# V1d.net
KiCad netlist of a schematic drawn in EAGLE
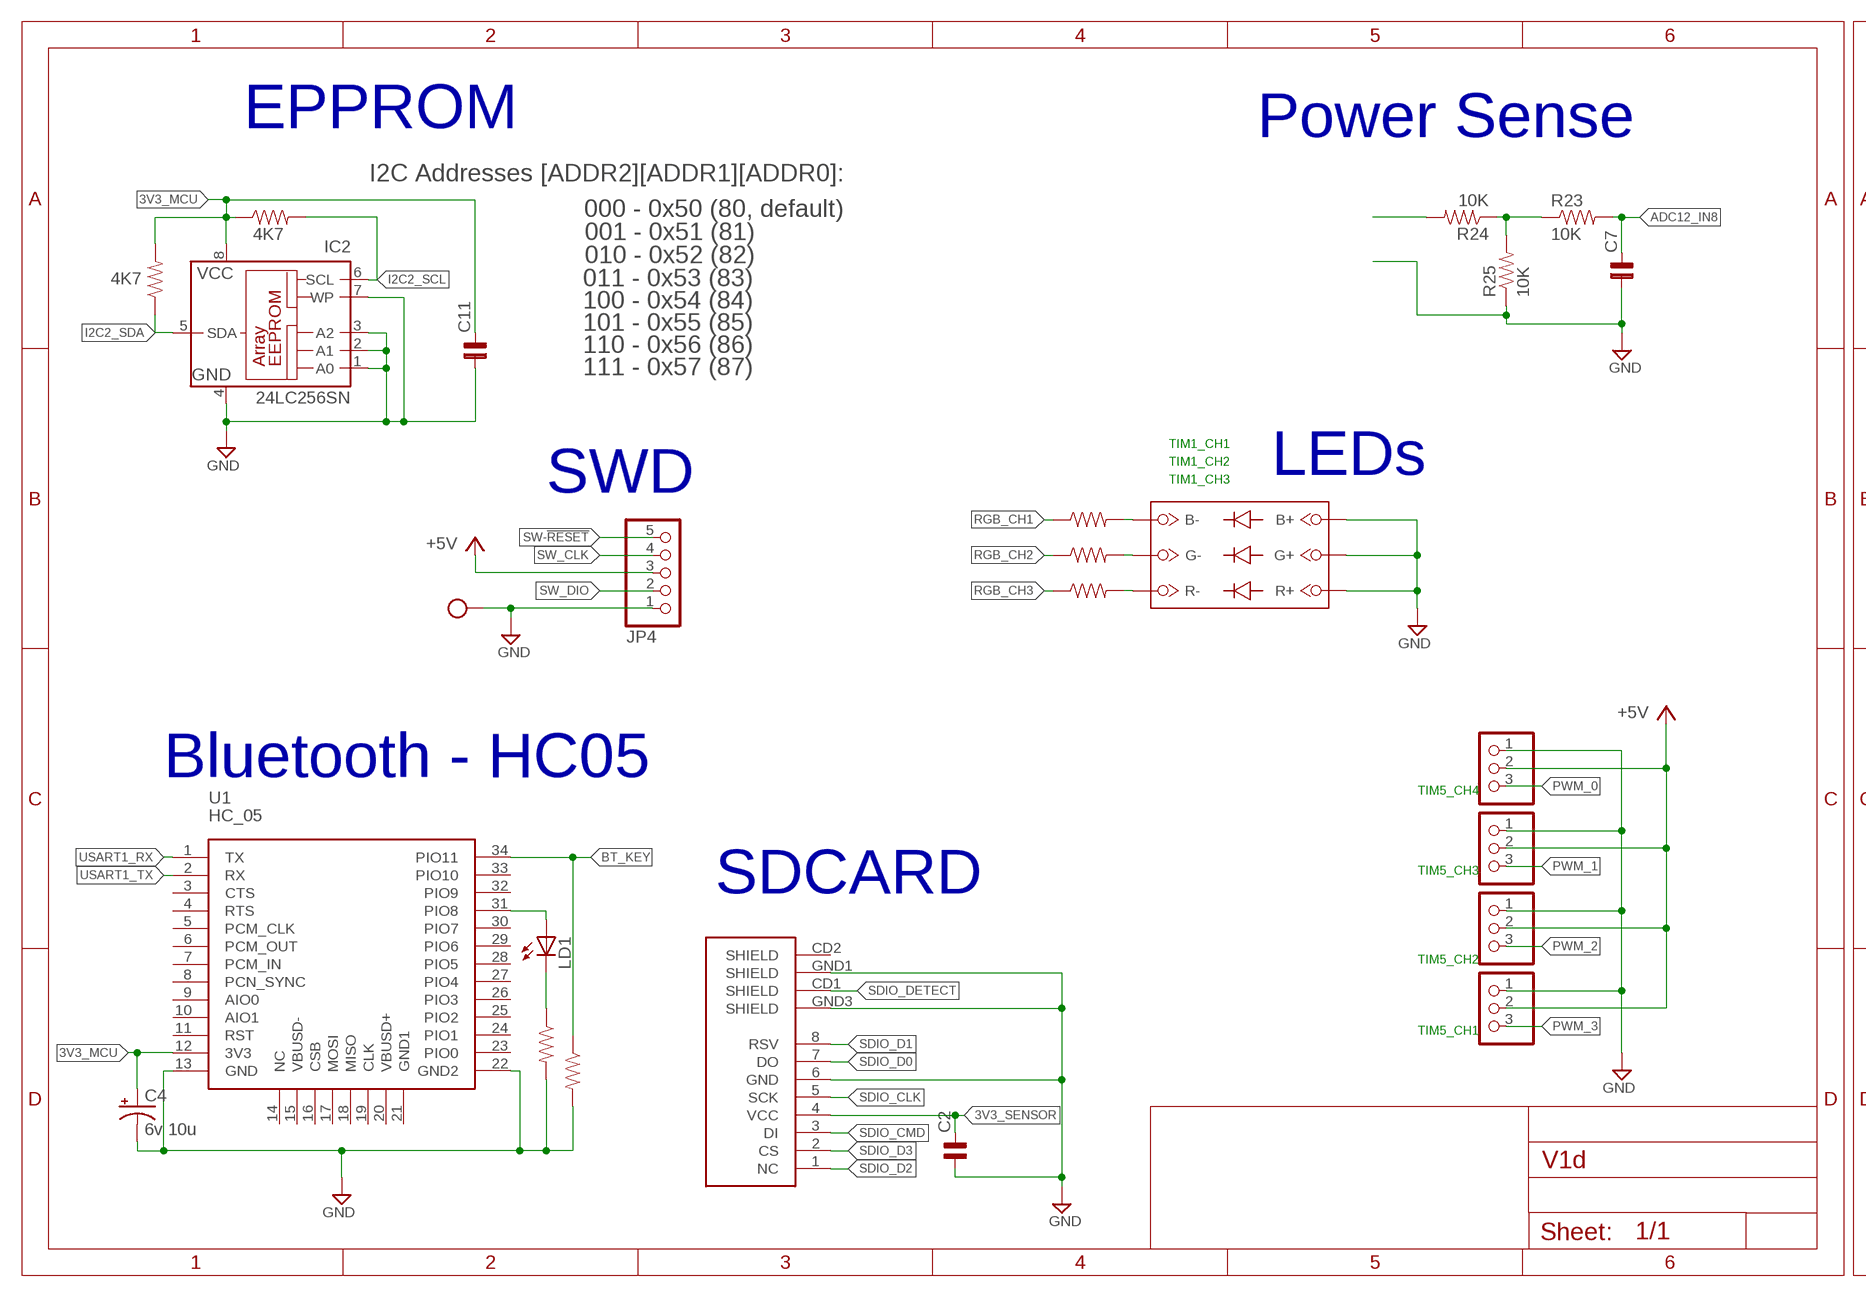
[diagram p0: schematic, sheet 1, part 1 of 2]
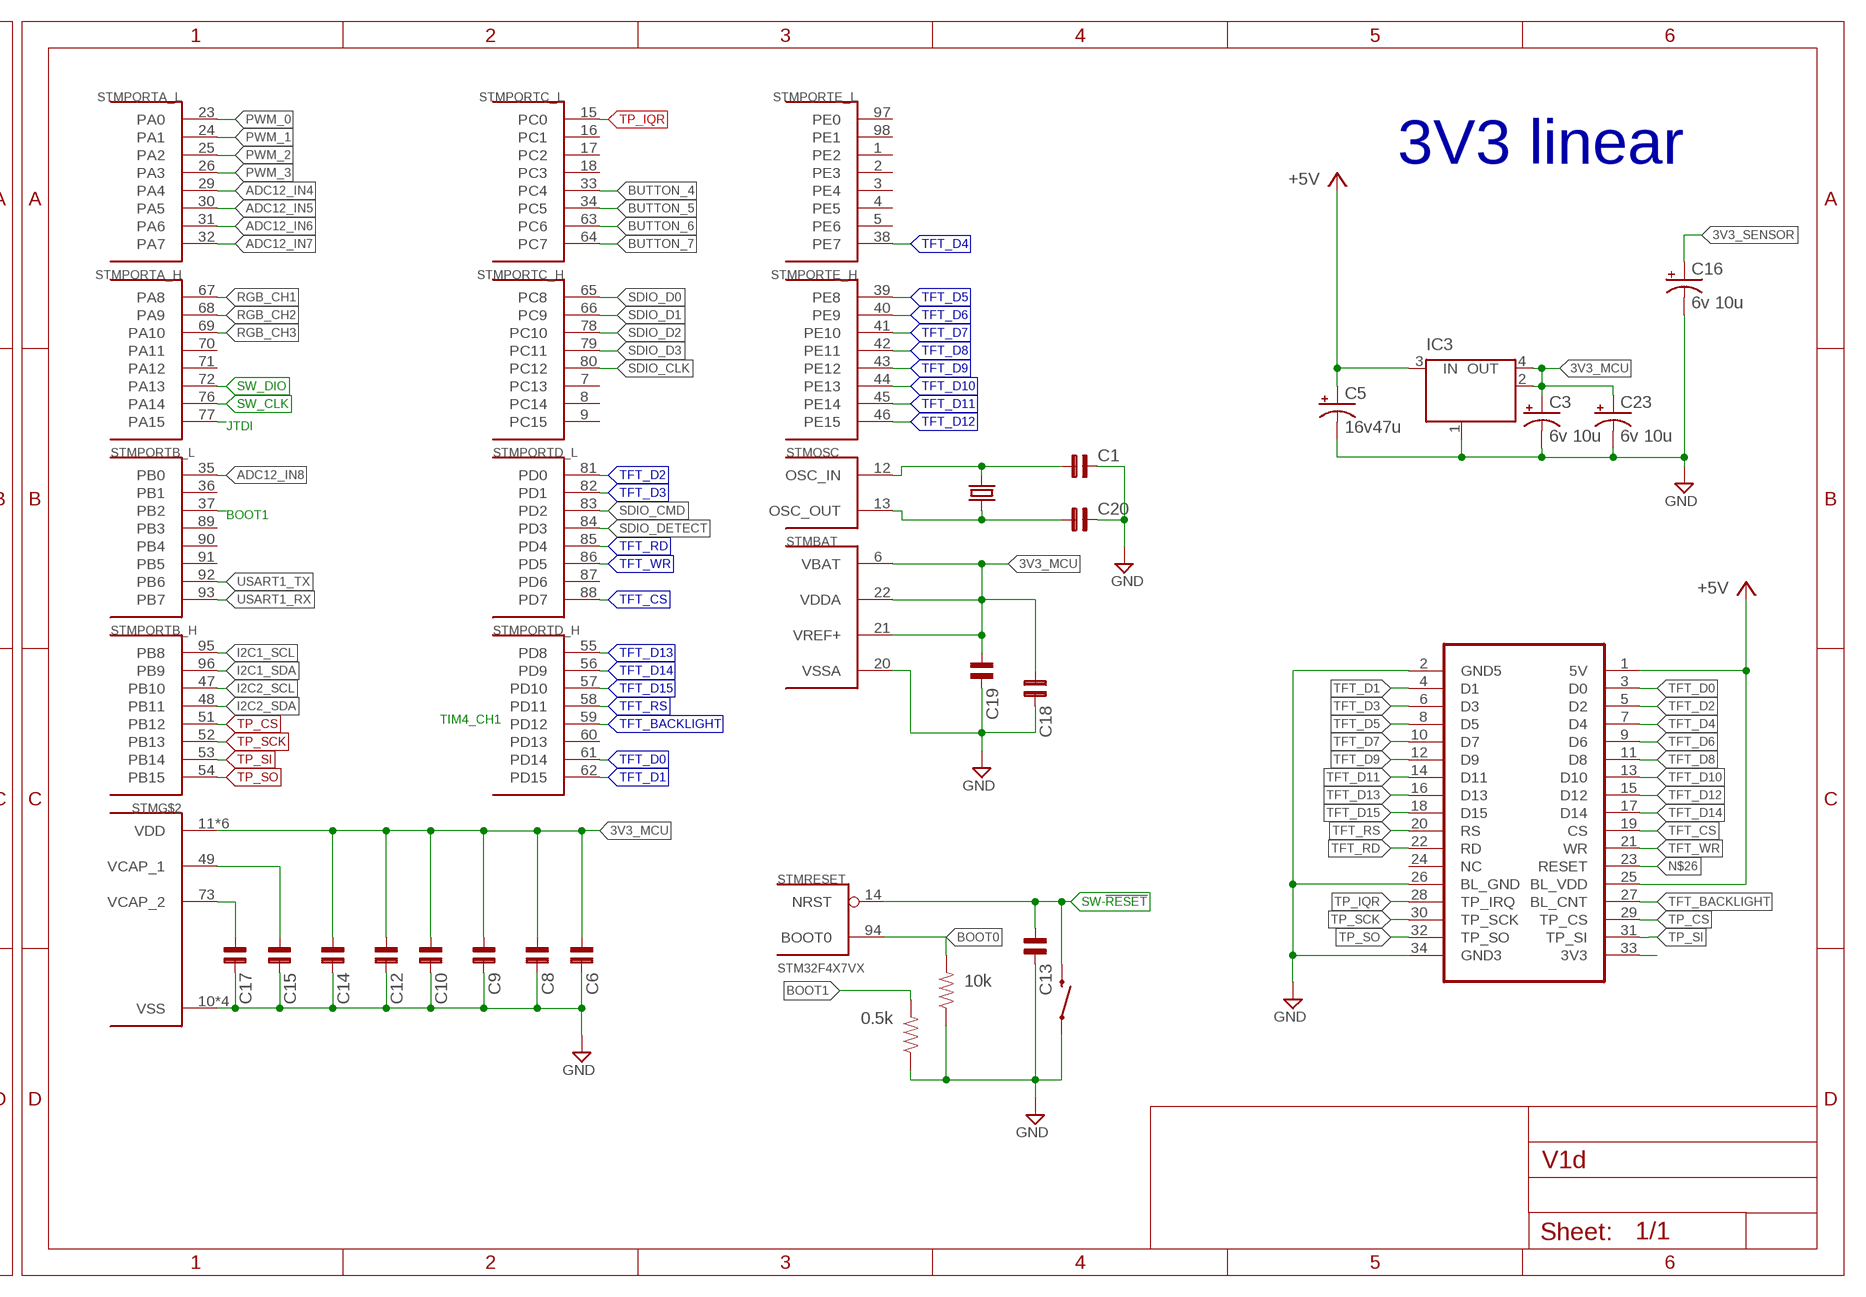
[diagram p1: schematic, sheet 1, part 2 of 2]

(export (version "E")
  (design (tool "Eeschema 10.0.6"))
  (components
    (comp (ref "C1")
      (value "C-NP-SMD-0603")
      (footprint "eagle-import:C-0603")
      (libsource (lib "eagle-import") (part "C-NP-SMD-0603"))
    )
    (comp (ref "C2")
      (value "C-NP-SMD-0603")
      (footprint "eagle-import:C-0603")
      (libsource (lib "eagle-import") (part "C-NP-SMD-0603"))
    )
    (comp (ref "C3")
      (value "6v 10u")
      (footprint "eagle-import:SMC_A")
      (libsource (lib "eagle-import") (part "CPOL-USSMCA"))
    )
    (comp (ref "C4")
      (value "6v 10u")
      (footprint "eagle-import:SMC_A")
      (libsource (lib "eagle-import") (part "CPOL-USSMCA"))
    )
    (comp (ref "C5")
      (value "16v47u")
      (footprint "eagle-import:SMC_C")
      (libsource (lib "eagle-import") (part "CPOL-USSMCC"))
    )
    (comp (ref "C6")
      (value "C-NP-SMD-0603")
      (footprint "eagle-import:C-0603")
      (libsource (lib "eagle-import") (part "C-NP-SMD-0603"))
    )
    (comp (ref "C7")
      (value "C-NP-SMD-0603")
      (footprint "eagle-import:C-0603")
      (libsource (lib "eagle-import") (part "C-NP-SMD-0603"))
    )
    (comp (ref "C8")
      (value "C-NP-SMD-0603")
      (footprint "eagle-import:C-0603")
      (libsource (lib "eagle-import") (part "C-NP-SMD-0603"))
    )
    (comp (ref "C9")
      (value "C-NP-SMD-0603")
      (footprint "eagle-import:C-0603")
      (libsource (lib "eagle-import") (part "C-NP-SMD-0603"))
    )
    (comp (ref "C10")
      (value "C-NP-SMD-0603")
      (footprint "eagle-import:C-0603")
      (libsource (lib "eagle-import") (part "C-NP-SMD-0603"))
    )
    (comp (ref "C11")
      (value "C-NP-SMD-0603")
      (footprint "eagle-import:C-0603")
      (libsource (lib "eagle-import") (part "C-NP-SMD-0603"))
    )
    (comp (ref "C12")
      (value "C-NP-SMD-0603")
      (footprint "eagle-import:C-0603")
      (libsource (lib "eagle-import") (part "C-NP-SMD-0603"))
    )
    (comp (ref "C13")
      (value "C-NP-SMD-0603")
      (footprint "eagle-import:C-0603")
      (libsource (lib "eagle-import") (part "C-NP-SMD-0603"))
    )
    (comp (ref "C14")
      (value "C-NP-SMD-0603")
      (footprint "eagle-import:C-0603")
      (libsource (lib "eagle-import") (part "C-NP-SMD-0603"))
    )
    (comp (ref "C15")
      (value "C-NP-SMD-0603")
      (footprint "eagle-import:C-0603")
      (libsource (lib "eagle-import") (part "C-NP-SMD-0603"))
    )
    (comp (ref "C16")
      (value "6v 10u")
      (footprint "eagle-import:SMC_A")
      (libsource (lib "eagle-import") (part "CPOL-USSMCA"))
    )
    (comp (ref "C17")
      (value "C-NP-SMD-0603")
      (footprint "eagle-import:C-0603")
      (libsource (lib "eagle-import") (part "C-NP-SMD-0603"))
    )
    (comp (ref "C18")
      (value "C-NP-SMD-0603")
      (footprint "eagle-import:C-0603")
      (libsource (lib "eagle-import") (part "C-NP-SMD-0603"))
    )
    (comp (ref "C19")
      (value "C-NP-SMD-0603")
      (footprint "eagle-import:C-0603")
      (libsource (lib "eagle-import") (part "C-NP-SMD-0603"))
    )
    (comp (ref "C20")
      (value "C-NP-SMD-0603")
      (footprint "eagle-import:C-0603")
      (libsource (lib "eagle-import") (part "C-NP-SMD-0603"))
    )
    (comp (ref "C23")
      (value "6v 10u")
      (footprint "eagle-import:SMC_A")
      (libsource (lib "eagle-import") (part "CPOL-USSMCA"))
    )
    (comp (ref "IC2")
      (value "24LC256SN")
      (footprint "eagle-import:SO-08")
      (fields (field (name "MF") "MICROCHIP") (field (name "MPN") "24LC256-I/SN"))
      (libsource (lib "eagle-import") (part "24SNLC256"))
    )
    (comp (ref "IC3")
      (value "LINEAR_MC33269ST-3.3T3")
      (footprint "eagle-import:LINEAR_SOT223")
      (libsource (lib "eagle-import") (part "LINEAR_MC33269ST-3.3T3"))
    )
    (comp (ref "JP1")
      (value "PINHD-1X3_2.54-90°")
      (footprint "eagle-import:1X03_90")
      (libsource (lib "eagle-import") (part "PINHD-1X3_2.54-90°"))
    )
    (comp (ref "JP4")
      (value "PINHD-1X5_2.54-90°")
      (footprint "eagle-import:1X05_90")
      (libsource (lib "eagle-import") (part "PINHD-1X5_2.54-90°"))
    )
    (comp (ref "JP5")
      (value "PINHD-1X3_2.54-90°")
      (footprint "eagle-import:1X03_90")
      (libsource (lib "eagle-import") (part "PINHD-1X3_2.54-90°"))
    )
    (comp (ref "JP6")
      (value "PINHD-1X3_2.54-90°")
      (footprint "eagle-import:1X03_90")
      (libsource (lib "eagle-import") (part "PINHD-1X3_2.54-90°"))
    )
    (comp (ref "JP11")
      (value "PINHD-1X3_2.54-90°")
      (footprint "eagle-import:1X03_90")
      (libsource (lib "eagle-import") (part "PINHD-1X3_2.54-90°"))
    )
    (comp (ref "LD1")
      (value "LEDCHIPLED_0805")
      (footprint "eagle-import:CHIPLED_0805")
      (libsource (lib "eagle-import") (part "LEDCHIPLED_0805"))
    )
    (comp (ref "R2")
      (value "10K")
      (footprint "eagle-import:SPARKFUN_0603-RES")
      (libsource (lib "eagle-import") (part "SPARKFUN_RESISTOR0603-RES"))
    )
    (comp (ref "R3")
      (value "10K")
      (footprint "eagle-import:SPARKFUN_0603-RES")
      (libsource (lib "eagle-import") (part "SPARKFUN_RESISTOR0603-RES"))
    )
    (comp (ref "R5")
      (value "10K")
      (footprint "eagle-import:SPARKFUN_0603-RES")
      (libsource (lib "eagle-import") (part "SPARKFUN_RESISTOR0603-RES"))
    )
    (comp (ref "R6")
      (value "10K")
      (footprint "eagle-import:SPARKFUN_0603-RES")
      (libsource (lib "eagle-import") (part "SPARKFUN_RESISTOR0603-RES"))
    )
    (comp (ref "R7")
      (value "10k")
      (footprint "eagle-import:SPARKFUN_0603-RES")
      (libsource (lib "eagle-import") (part "SPARKFUN_RESISTOR0603-RES"))
    )
    (comp (ref "R8")
      (value "0.5k")
      (footprint "eagle-import:SPARKFUN_0603-RES")
      (libsource (lib "eagle-import") (part "SPARKFUN_RESISTOR0603-RES"))
    )
    (comp (ref "R9")
      (value "10K")
      (footprint "eagle-import:SPARKFUN_0603-RES")
      (libsource (lib "eagle-import") (part "SPARKFUN_RESISTOR0603-RES"))
    )
    (comp (ref "R15")
      (value "4K7")
      (footprint "eagle-import:SPARKFUN_0603-RES")
      (libsource (lib "eagle-import") (part "SPARKFUN_RESISTOR0603-RES"))
    )
    (comp (ref "R16")
      (value "4K7")
      (footprint "eagle-import:SPARKFUN_0603-RES")
      (libsource (lib "eagle-import") (part "SPARKFUN_RESISTOR0603-RES"))
    )
    (comp (ref "R23")
      (value "10K")
      (footprint "eagle-import:SPARKFUN_0603-RES")
      (libsource (lib "eagle-import") (part "SPARKFUN_RESISTOR0603-RES"))
    )
    (comp (ref "R24")
      (value "10K")
      (footprint "eagle-import:SPARKFUN_0603-RES")
      (libsource (lib "eagle-import") (part "SPARKFUN_RESISTOR0603-RES"))
    )
    (comp (ref "R25")
      (value "10K")
      (footprint "eagle-import:SPARKFUN_0603-RES")
      (libsource (lib "eagle-import") (part "SPARKFUN_RESISTOR0603-RES"))
    )
    (comp (ref "S1")
      (value "RESET")
      (footprint "eagle-import:TACTILE-SWITCH-1101NE")
      (fields (field (name "PARTNO") "EVQ-P7J01P"))
      (libsource (lib "eagle-import") (part "SWITCH-MOMENTARY-2-SMD-1101NE"))
    )
    (comp (ref "SDCARD2")
      (value "microSD Socket")
      (footprint "eagle-import:MICRO-SD-SOCKET-PP")
      (libsource (lib "eagle-import") (part "USD-SOCKETNEW"))
    )
    (comp (ref "STM")
      (value "STM32F4X7VX")
      (footprint "eagle-import:TQFP100")
      (fields (field (name "PARTNO") "STM32F427VI"))
      (libsource (lib "eagle-import") (part "STM32F4X7VX"))
    )
    (comp (ref "U$3")
      (value "TFT3.2")
      (footprint "eagle-import:HY32D_2")
      (libsource (lib "eagle-import") (part "TFT3.2"))
    )
    (comp (ref "U$12")
      (value "RGB_LED")
      (footprint "eagle-import:SMD")
      (libsource (lib "eagle-import") (part "RGB_LED"))
    )
    (comp (ref "U1")
      (value "HC_05")
      (footprint "eagle-import:BLUETOOTH_SMD")
      (libsource (lib "eagle-import") (part "HC_05"))
    )
    (comp (ref "X1")
      (value "MKDSN1,5/2-5,08")
      (footprint "eagle-import:MKDSN1,5_2-5,08")
      (fields (field (name "MPN") "MKDSN 1,5/2-5.08"))
      (libsource (lib "eagle-import") (part "MKDSN1,5/2-5,08"))
    )
    (comp (ref "Y1")
      (value "CRYSTALHC49US")
      (footprint "eagle-import:HC49US")
      (libsource (lib "eagle-import") (part "CRYSTALHC49US"))
    )
  )
  (nets
    (net (code "1") (name "+5V") (class "Default")
      (node (ref "C5") (pin "+") (pinfunction "+_+") (pintype "passive"))
      (node (ref "IC3") (pin "3") (pinfunction "IN_3") (pintype "input"))
      (node (ref "JP1") (pin "2") (pinfunction "2_2") (pintype "passive"))
      (node (ref "JP11") (pin "2") (pinfunction "2_2") (pintype "passive"))
      (node (ref "JP4") (pin "3") (pinfunction "3_3") (pintype "passive"))
      (node (ref "JP5") (pin "2") (pinfunction "2_2") (pintype "passive"))
      (node (ref "JP6") (pin "2") (pinfunction "2_2") (pintype "passive"))
      (node (ref "U$3") (pin "1") (pinfunction "5V_1") (pintype "bidirectional"))
      (node (ref "U$3") (pin "25") (pinfunction "BL_VDD_25") (pintype "bidirectional"))
    )
    (net (code "2") (name "/JTDI") (class "Default")
      (node (ref "STM") (pin "77") (pinfunction "PA15_77") (pintype "bidirectional"))
    )
    (net (code "3") (name "/SW-~{RESET}") (class "Default")
      (node (ref "C13") (pin "1") (pinfunction "1_1") (pintype "passive"))
      (node (ref "JP4") (pin "5") (pinfunction "5_5") (pintype "passive"))
      (node (ref "S1") (pin "P$2") (pinfunction "2_P$2") (pintype "passive"))
      (node (ref "STM") (pin "14") (pinfunction "NRST_14") (pintype "input"))
    )
    (net (code "4") (name "3V3_MCU") (class "Default")
      (node (ref "C10") (pin "1") (pinfunction "1_1") (pintype "passive"))
      (node (ref "C11") (pin "2") (pinfunction "2_2") (pintype "passive"))
      (node (ref "C12") (pin "1") (pinfunction "1_1") (pintype "passive"))
      (node (ref "C14") (pin "1") (pinfunction "1_1") (pintype "passive"))
      (node (ref "C18") (pin "1") (pinfunction "1_1") (pintype "passive"))
      (node (ref "C19") (pin "1") (pinfunction "1_1") (pintype "passive"))
      (node (ref "C23") (pin "+") (pinfunction "+_+") (pintype "passive"))
      (node (ref "C3") (pin "+") (pinfunction "+_+") (pintype "passive"))
      (node (ref "C4") (pin "+") (pinfunction "+_+") (pintype "passive"))
      (node (ref "C6") (pin "1") (pinfunction "1_1") (pintype "passive"))
      (node (ref "C8") (pin "1") (pinfunction "1_1") (pintype "passive"))
      (node (ref "C9") (pin "1") (pinfunction "1_1") (pintype "passive"))
      (node (ref "IC2") (pin "8") (pinfunction "VCC_8") (pintype "power_in"))
      (node (ref "IC3") (pin "2") (pinfunction "OUT_2") (pintype "passive"))
      (node (ref "IC3") (pin "4") (pinfunction "OUT_4") (pintype "passive"))
      (node (ref "R15") (pin "1") (pinfunction "1_1") (pintype "passive"))
      (node (ref "R16") (pin "2") (pinfunction "2_2") (pintype "passive"))
      (node (ref "STM") (pin "100") (pinfunction "VDD_100") (pintype "power_in"))
      (node (ref "STM") (pin "11") (pinfunction "VDD_11") (pintype "power_in"))
      (node (ref "STM") (pin "19") (pinfunction "VDD_19") (pintype "power_in"))
      (node (ref "STM") (pin "21") (pinfunction "VREF+_21") (pintype "input"))
      (node (ref "STM") (pin "22") (pinfunction "VDDA_22") (pintype "power_in"))
      (node (ref "STM") (pin "28") (pinfunction "VDD_28") (pintype "power_in"))
      (node (ref "STM") (pin "50") (pinfunction "VDD_50") (pintype "power_in"))
      (node (ref "STM") (pin "6") (pinfunction "VBAT_6") (pintype "power_in"))
      (node (ref "STM") (pin "75") (pinfunction "VDD_75") (pintype "power_in"))
      (node (ref "U1") (pin "12") (pinfunction "3V3_12") (pintype "bidirectional"))
    )
    (net (code "5") (name "3V3_SENSOR") (class "Default")
      (node (ref "C16") (pin "+") (pinfunction "+_+") (pintype "passive"))
      (node (ref "C2") (pin "2") (pinfunction "2_2") (pintype "passive"))
      (node (ref "SDCARD2") (pin "4") (pinfunction "VCC_4") (pintype "bidirectional"))
    )
    (net (code "6") (name "ADC12_IN4") (class "Default")
      (node (ref "STM") (pin "29") (pinfunction "PA4_29") (pintype "bidirectional"))
    )
    (net (code "7") (name "ADC12_IN5") (class "Default")
      (node (ref "STM") (pin "30") (pinfunction "PA5_30") (pintype "bidirectional"))
    )
    (net (code "8") (name "ADC12_IN6") (class "Default")
      (node (ref "STM") (pin "31") (pinfunction "PA6_31") (pintype "bidirectional"))
    )
    (net (code "9") (name "ADC12_IN7") (class "Default")
      (node (ref "STM") (pin "32") (pinfunction "PA7_32") (pintype "bidirectional"))
    )
    (net (code "10") (name "ADC12_IN8") (class "Default")
      (node (ref "C7") (pin "2") (pinfunction "2_2") (pintype "passive"))
      (node (ref "R23") (pin "2") (pinfunction "2_2") (pintype "passive"))
      (node (ref "STM") (pin "35") (pinfunction "PB0_35") (pintype "bidirectional"))
    )
    (net (code "11") (name "BOOT0") (class "Default")
      (node (ref "R7") (pin "2") (pinfunction "2_2") (pintype "passive"))
      (node (ref "STM") (pin "94") (pinfunction "BOOT0_94") (pintype "input"))
    )
    (net (code "12") (name "BOOT1") (class "Default")
      (node (ref "R8") (pin "2") (pinfunction "2_2") (pintype "passive"))
      (node (ref "STM") (pin "37") (pinfunction "PB2_37") (pintype "bidirectional"))
    )
    (net (code "13") (name "BT_KEY") (class "Default")
      (node (ref "R5") (pin "1") (pinfunction "1_1") (pintype "passive"))
      (node (ref "U1") (pin "34") (pinfunction "PIO11_34") (pintype "bidirectional"))
    )
    (net (code "14") (name "BUTTON_4") (class "Default")
      (node (ref "STM") (pin "33") (pinfunction "PC4_33") (pintype "bidirectional"))
    )
    (net (code "15") (name "BUTTON_5") (class "Default")
      (node (ref "STM") (pin "34") (pinfunction "PC5_34") (pintype "bidirectional"))
    )
    (net (code "16") (name "BUTTON_6") (class "Default")
      (node (ref "STM") (pin "63") (pinfunction "PC6_63") (pintype "bidirectional"))
    )
    (net (code "17") (name "BUTTON_7") (class "Default")
      (node (ref "STM") (pin "64") (pinfunction "PC7_64") (pintype "bidirectional"))
    )
    (net (code "18") (name "GND") (class "Default")
      (node (ref "C1") (pin "2") (pinfunction "2_2") (pintype "passive"))
      (node (ref "C10") (pin "2") (pinfunction "2_2") (pintype "passive"))
      (node (ref "C11") (pin "1") (pinfunction "1_1") (pintype "passive"))
      (node (ref "C12") (pin "2") (pinfunction "2_2") (pintype "passive"))
      (node (ref "C13") (pin "2") (pinfunction "2_2") (pintype "passive"))
      (node (ref "C14") (pin "2") (pinfunction "2_2") (pintype "passive"))
      (node (ref "C15") (pin "2") (pinfunction "2_2") (pintype "passive"))
      (node (ref "C16") (pin "-") (pinfunction "-_-") (pintype "passive"))
      (node (ref "C17") (pin "2") (pinfunction "2_2") (pintype "passive"))
      (node (ref "C18") (pin "2") (pinfunction "2_2") (pintype "passive"))
      (node (ref "C19") (pin "2") (pinfunction "2_2") (pintype "passive"))
      (node (ref "C2") (pin "1") (pinfunction "1_1") (pintype "passive"))
      (node (ref "C20") (pin "2") (pinfunction "2_2") (pintype "passive"))
      (node (ref "C23") (pin "-") (pinfunction "-_-") (pintype "passive"))
      (node (ref "C3") (pin "-") (pinfunction "-_-") (pintype "passive"))
      (node (ref "C4") (pin "-") (pinfunction "-_-") (pintype "passive"))
      (node (ref "C5") (pin "-") (pinfunction "-_-") (pintype "passive"))
      (node (ref "C6") (pin "2") (pinfunction "2_2") (pintype "passive"))
      (node (ref "C7") (pin "1") (pinfunction "1_1") (pintype "passive"))
      (node (ref "C8") (pin "2") (pinfunction "2_2") (pintype "passive"))
      (node (ref "C9") (pin "2") (pinfunction "2_2") (pintype "passive"))
      (node (ref "IC2") (pin "1") (pinfunction "A0_1") (pintype "input"))
      (node (ref "IC2") (pin "2") (pinfunction "A1_2") (pintype "input"))
      (node (ref "IC2") (pin "3") (pinfunction "A2_3") (pintype "input"))
      (node (ref "IC2") (pin "4") (pinfunction "GND_4") (pintype "power_in"))
      (node (ref "IC2") (pin "7") (pinfunction "WP_7") (pintype "input"))
      (node (ref "IC3") (pin "1") (pinfunction "GND/ADJ_1") (pintype "input"))
      (node (ref "JP1") (pin "1") (pinfunction "1_1") (pintype "passive"))
      (node (ref "JP11") (pin "1") (pinfunction "1_1") (pintype "passive"))
      (node (ref "JP4") (pin "1") (pinfunction "1_1") (pintype "passive"))
      (node (ref "JP5") (pin "1") (pinfunction "1_1") (pintype "passive"))
      (node (ref "JP6") (pin "1") (pinfunction "1_1") (pintype "passive"))
      (node (ref "R25") (pin "1") (pinfunction "1_1") (pintype "passive"))
      (node (ref "R5") (pin "2") (pinfunction "2_2") (pintype "passive"))
      (node (ref "R7") (pin "1") (pinfunction "1_1") (pintype "passive"))
      (node (ref "R8") (pin "1") (pinfunction "1_1") (pintype "passive"))
      (node (ref "R9") (pin "2") (pinfunction "2_2") (pintype "passive"))
      (node (ref "S1") (pin "P$1") (pinfunction "1_P$1") (pintype "passive"))
      (node (ref "SDCARD2") (pin "6") (pinfunction "GND_6") (pintype "bidirectional"))
      (node (ref "SDCARD2") (pin "GND1") (pinfunction "SHIELD_GND1") (pintype "bidirectional"))
      (node (ref "SDCARD2") (pin "GND3") (pinfunction "SHIELD_GND3") (pintype "bidirectional"))
      (node (ref "STM") (pin "10") (pinfunction "VSS_10") (pintype "power_in"))
      (node (ref "STM") (pin "20") (pinfunction "VSSA_20") (pintype "power_in"))
      (node (ref "STM") (pin "27") (pinfunction "VSS_27") (pintype "power_in"))
      (node (ref "STM") (pin "74") (pinfunction "VSS_74") (pintype "power_in"))
      (node (ref "STM") (pin "99") (pinfunction "VSS_99") (pintype "power_in"))
      (node (ref "U$12") (pin "B+") (pinfunction "B+_B+") (pintype "bidirectional"))
      (node (ref "U$12") (pin "G+") (pinfunction "G+_G+") (pintype "bidirectional"))
      (node (ref "U$12") (pin "R+") (pinfunction "R+_R+") (pintype "bidirectional"))
      (node (ref "U$3") (pin "2") (pinfunction "GND5_2") (pintype "bidirectional"))
      (node (ref "U$3") (pin "26") (pinfunction "BL_GND_26") (pintype "bidirectional"))
      (node (ref "U$3") (pin "34") (pinfunction "GND3_34") (pintype "bidirectional"))
      (node (ref "U1") (pin "13") (pinfunction "GND_13") (pintype "bidirectional"))
      (node (ref "U1") (pin "22") (pinfunction "GND2_22") (pintype "bidirectional"))
      (node (ref "X1") (pin "2") (pinfunction "KL_2") (pintype "passive"))
    )
    (net (code "19") (name "I2C1_SCL") (class "Default")
      (node (ref "STM") (pin "95") (pinfunction "PB8_95") (pintype "bidirectional"))
    )
    (net (code "20") (name "I2C1_SDA") (class "Default")
      (node (ref "STM") (pin "96") (pinfunction "PB9_96") (pintype "bidirectional"))
    )
    (net (code "21") (name "I2C2_SCL") (class "Default")
      (node (ref "IC2") (pin "6") (pinfunction "SCL_6") (pintype "input"))
      (node (ref "R15") (pin "2") (pinfunction "2_2") (pintype "passive"))
      (node (ref "STM") (pin "47") (pinfunction "PB10_47") (pintype "bidirectional"))
    )
    (net (code "22") (name "I2C2_SDA") (class "Default")
      (node (ref "IC2") (pin "5") (pinfunction "SDA_5") (pintype "bidirectional"))
      (node (ref "R16") (pin "1") (pinfunction "1_1") (pintype "passive"))
      (node (ref "STM") (pin "48") (pinfunction "PB11_48") (pintype "bidirectional"))
    )
    (net (code "23") (name "N$26") (class "Default")
      (node (ref "U$3") (pin "23") (pinfunction "RESET_23") (pintype "bidirectional"))
    )
    (net (code "24") (name "Net-(LD1-PadC)") (class "Default")
      (node (ref "LD1") (pin "C") (pinfunction "C_C") (pintype "passive"))
      (node (ref "R9") (pin "1") (pinfunction "1_1") (pintype "passive"))
    )
    (net (code "25") (name "Net-(R2-Pad2)") (class "Default")
      (node (ref "R2") (pin "2") (pinfunction "2_2") (pintype "passive"))
      (node (ref "U$12") (pin "B-") (pinfunction "B-_B-") (pintype "bidirectional"))
    )
    (net (code "26") (name "Net-(R3-Pad2)") (class "Default")
      (node (ref "R3") (pin "2") (pinfunction "2_2") (pintype "passive"))
      (node (ref "U$12") (pin "G-") (pinfunction "G-_G-") (pintype "bidirectional"))
    )
    (net (code "27") (name "Net-(R6-Pad2)") (class "Default")
      (node (ref "R6") (pin "2") (pinfunction "2_2") (pintype "passive"))
      (node (ref "U$12") (pin "R-") (pinfunction "R-_R-") (pintype "bidirectional"))
    )
    (net (code "28") (name "Net-(R23-Pad1)") (class "Default")
      (node (ref "R23") (pin "1") (pinfunction "1_1") (pintype "passive"))
      (node (ref "R24") (pin "1") (pinfunction "1_1") (pintype "passive"))
      (node (ref "R25") (pin "2") (pinfunction "2_2") (pintype "passive"))
    )
    (net (code "29") (name "Net-(STMB-VCAP_1)") (class "Default")
      (node (ref "C15") (pin "1") (pinfunction "1_1") (pintype "passive"))
      (node (ref "STM") (pin "49") (pinfunction "VCAP_1_49") (pintype "power_in"))
    )
    (net (code "30") (name "Net-(STMB-VCAP_2)") (class "Default")
      (node (ref "C17") (pin "1") (pinfunction "1_1") (pintype "passive"))
      (node (ref "STM") (pin "73") (pinfunction "VCAP_2_73") (pintype "power_in"))
    )
    (net (code "31") (name "Net-(STMC-OSC_IN)") (class "Default")
      (node (ref "C1") (pin "1") (pinfunction "1_1") (pintype "passive"))
      (node (ref "STM") (pin "12") (pinfunction "OSC_IN_12") (pintype "input"))
      (node (ref "Y1") (pin "2") (pinfunction "2_2") (pintype "passive"))
    )
    (net (code "32") (name "Net-(STMC-OSC_OUT)") (class "Default")
      (node (ref "C20") (pin "1") (pinfunction "1_1") (pintype "passive"))
      (node (ref "STM") (pin "13") (pinfunction "OSC_OUT_13") (pintype "output"))
      (node (ref "Y1") (pin "1") (pinfunction "1_1") (pintype "passive"))
    )
    (net (code "33") (name "Net-(U1-PIO8)") (class "Default")
      (node (ref "LD1") (pin "A") (pinfunction "A_A") (pintype "passive"))
      (node (ref "U1") (pin "31") (pinfunction "PIO8_31") (pintype "bidirectional"))
    )
    (net (code "34") (name "PWM_0") (class "Default")
      (node (ref "JP6") (pin "3") (pinfunction "3_3") (pintype "passive"))
      (node (ref "STM") (pin "23") (pinfunction "PA0_23") (pintype "bidirectional"))
    )
    (net (code "35") (name "PWM_1") (class "Default")
      (node (ref "JP11") (pin "3") (pinfunction "3_3") (pintype "passive"))
      (node (ref "STM") (pin "24") (pinfunction "PA1_24") (pintype "bidirectional"))
    )
    (net (code "36") (name "PWM_2") (class "Default")
      (node (ref "JP5") (pin "3") (pinfunction "3_3") (pintype "passive"))
      (node (ref "STM") (pin "25") (pinfunction "PA2_25") (pintype "bidirectional"))
    )
    (net (code "37") (name "PWM_3") (class "Default")
      (node (ref "JP1") (pin "3") (pinfunction "3_3") (pintype "passive"))
      (node (ref "STM") (pin "26") (pinfunction "PA3_26") (pintype "bidirectional"))
    )
    (net (code "38") (name "RGB_CH1") (class "Default")
      (node (ref "R2") (pin "1") (pinfunction "1_1") (pintype "passive"))
      (node (ref "STM") (pin "67") (pinfunction "PA8_67") (pintype "bidirectional"))
    )
    (net (code "39") (name "RGB_CH2") (class "Default")
      (node (ref "R3") (pin "1") (pinfunction "1_1") (pintype "passive"))
      (node (ref "STM") (pin "68") (pinfunction "PA9_68") (pintype "bidirectional"))
    )
    (net (code "40") (name "RGB_CH3") (class "Default")
      (node (ref "R6") (pin "1") (pinfunction "1_1") (pintype "passive"))
      (node (ref "STM") (pin "69") (pinfunction "PA10_69") (pintype "bidirectional"))
    )
    (net (code "41") (name "SDIO_CLK") (class "Default")
      (node (ref "SDCARD2") (pin "5") (pinfunction "SCK_5") (pintype "bidirectional"))
      (node (ref "STM") (pin "80") (pinfunction "PC12_80") (pintype "bidirectional"))
    )
    (net (code "42") (name "SDIO_CMD") (class "Default")
      (node (ref "SDCARD2") (pin "3") (pinfunction "DI_3") (pintype "bidirectional"))
      (node (ref "STM") (pin "83") (pinfunction "PD2_83") (pintype "bidirectional"))
    )
    (net (code "43") (name "SDIO_D0") (class "Default")
      (node (ref "SDCARD2") (pin "7") (pinfunction "DO_7") (pintype "bidirectional"))
      (node (ref "STM") (pin "65") (pinfunction "PC8_65") (pintype "bidirectional"))
    )
    (net (code "44") (name "SDIO_D1") (class "Default")
      (node (ref "SDCARD2") (pin "8") (pinfunction "RSV_8") (pintype "bidirectional"))
      (node (ref "STM") (pin "66") (pinfunction "PC9_66") (pintype "bidirectional"))
    )
    (net (code "45") (name "SDIO_D2") (class "Default")
      (node (ref "SDCARD2") (pin "1") (pinfunction "NC_1") (pintype "bidirectional"))
      (node (ref "STM") (pin "78") (pinfunction "PC10_78") (pintype "bidirectional"))
    )
    (net (code "46") (name "SDIO_D3") (class "Default")
      (node (ref "SDCARD2") (pin "2") (pinfunction "CS_2") (pintype "bidirectional"))
      (node (ref "STM") (pin "79") (pinfunction "PC11_79") (pintype "bidirectional"))
    )
    (net (code "47") (name "SDIO_DETECT") (class "Default")
      (node (ref "SDCARD2") (pin "CD1") (pinfunction "SHIELD_CD1") (pintype "bidirectional"))
      (node (ref "STM") (pin "84") (pinfunction "PD3_84") (pintype "bidirectional"))
    )
    (net (code "48") (name "SW_CLK") (class "Default")
      (node (ref "JP4") (pin "4") (pinfunction "4_4") (pintype "passive"))
      (node (ref "STM") (pin "76") (pinfunction "PA14_76") (pintype "bidirectional"))
    )
    (net (code "49") (name "SW_DIO") (class "Default")
      (node (ref "JP4") (pin "2") (pinfunction "2_2") (pintype "passive"))
      (node (ref "STM") (pin "72") (pinfunction "PA13_72") (pintype "bidirectional"))
    )
    (net (code "50") (name "TFT_BACKLIGHT") (class "Default")
      (node (ref "STM") (pin "59") (pinfunction "PD12_59") (pintype "bidirectional"))
      (node (ref "U$3") (pin "27") (pinfunction "BL_CNT_27") (pintype "bidirectional"))
    )
    (net (code "51") (name "TFT_CS") (class "Default")
      (node (ref "STM") (pin "88") (pinfunction "PD7_88") (pintype "bidirectional"))
      (node (ref "U$3") (pin "19") (pinfunction "CS_19") (pintype "bidirectional"))
    )
    (net (code "52") (name "TFT_D0") (class "Default")
      (node (ref "STM") (pin "61") (pinfunction "PD14_61") (pintype "bidirectional"))
      (node (ref "U$3") (pin "3") (pinfunction "D0_3") (pintype "bidirectional"))
    )
    (net (code "53") (name "TFT_D1") (class "Default")
      (node (ref "STM") (pin "62") (pinfunction "PD15_62") (pintype "bidirectional"))
      (node (ref "U$3") (pin "4") (pinfunction "D1_4") (pintype "bidirectional"))
    )
    (net (code "54") (name "TFT_D2") (class "Default")
      (node (ref "STM") (pin "81") (pinfunction "PD0_81") (pintype "bidirectional"))
      (node (ref "U$3") (pin "5") (pinfunction "D2_5") (pintype "bidirectional"))
    )
    (net (code "55") (name "TFT_D3") (class "Default")
      (node (ref "STM") (pin "82") (pinfunction "PD1_82") (pintype "bidirectional"))
      (node (ref "U$3") (pin "6") (pinfunction "D3_6") (pintype "bidirectional"))
    )
    (net (code "56") (name "TFT_D4") (class "Default")
      (node (ref "STM") (pin "38") (pinfunction "PE7_38") (pintype "bidirectional"))
      (node (ref "U$3") (pin "7") (pinfunction "D4_7") (pintype "bidirectional"))
    )
    (net (code "57") (name "TFT_D5") (class "Default")
      (node (ref "STM") (pin "39") (pinfunction "PE8_39") (pintype "bidirectional"))
      (node (ref "U$3") (pin "8") (pinfunction "D5_8") (pintype "bidirectional"))
    )
    (net (code "58") (name "TFT_D6") (class "Default")
      (node (ref "STM") (pin "40") (pinfunction "PE9_40") (pintype "bidirectional"))
      (node (ref "U$3") (pin "9") (pinfunction "D6_9") (pintype "bidirectional"))
    )
    (net (code "59") (name "TFT_D7") (class "Default")
      (node (ref "STM") (pin "41") (pinfunction "PE10_41") (pintype "bidirectional"))
      (node (ref "U$3") (pin "10") (pinfunction "D7_10") (pintype "bidirectional"))
    )
    (net (code "60") (name "TFT_D8") (class "Default")
      (node (ref "STM") (pin "42") (pinfunction "PE11_42") (pintype "bidirectional"))
      (node (ref "U$3") (pin "11") (pinfunction "D8_11") (pintype "bidirectional"))
    )
    (net (code "61") (name "TFT_D9") (class "Default")
      (node (ref "STM") (pin "43") (pinfunction "PE12_43") (pintype "bidirectional"))
      (node (ref "U$3") (pin "12") (pinfunction "D9_12") (pintype "bidirectional"))
    )
    (net (code "62") (name "TFT_D10") (class "Default")
      (node (ref "STM") (pin "44") (pinfunction "PE13_44") (pintype "bidirectional"))
      (node (ref "U$3") (pin "13") (pinfunction "D10_13") (pintype "bidirectional"))
    )
    (net (code "63") (name "TFT_D11") (class "Default")
      (node (ref "STM") (pin "45") (pinfunction "PE14_45") (pintype "bidirectional"))
      (node (ref "U$3") (pin "14") (pinfunction "D11_14") (pintype "bidirectional"))
    )
    (net (code "64") (name "TFT_D12") (class "Default")
      (node (ref "STM") (pin "46") (pinfunction "PE15_46") (pintype "bidirectional"))
      (node (ref "U$3") (pin "15") (pinfunction "D12_15") (pintype "bidirectional"))
    )
    (net (code "65") (name "TFT_D13") (class "Default")
      (node (ref "STM") (pin "55") (pinfunction "PD8_55") (pintype "bidirectional"))
      (node (ref "U$3") (pin "16") (pinfunction "D13_16") (pintype "bidirectional"))
    )
    (net (code "66") (name "TFT_D14") (class "Default")
      (node (ref "STM") (pin "56") (pinfunction "PD9_56") (pintype "bidirectional"))
      (node (ref "U$3") (pin "17") (pinfunction "D14_17") (pintype "bidirectional"))
    )
    (net (code "67") (name "TFT_D15") (class "Default")
      (node (ref "STM") (pin "57") (pinfunction "PD10_57") (pintype "bidirectional"))
      (node (ref "U$3") (pin "18") (pinfunction "D15_18") (pintype "bidirectional"))
    )
    (net (code "68") (name "TFT_RD") (class "Default")
      (node (ref "STM") (pin "85") (pinfunction "PD4_85") (pintype "bidirectional"))
      (node (ref "U$3") (pin "22") (pinfunction "RD_22") (pintype "bidirectional"))
    )
    (net (code "69") (name "TFT_RS") (class "Default")
      (node (ref "STM") (pin "58") (pinfunction "PD11_58") (pintype "bidirectional"))
      (node (ref "U$3") (pin "20") (pinfunction "RS_20") (pintype "bidirectional"))
    )
    (net (code "70") (name "TFT_WR") (class "Default")
      (node (ref "STM") (pin "86") (pinfunction "PD5_86") (pintype "bidirectional"))
      (node (ref "U$3") (pin "21") (pinfunction "WR_21") (pintype "bidirectional"))
    )
    (net (code "71") (name "TP_CS") (class "Default")
      (node (ref "STM") (pin "51") (pinfunction "PB12_51") (pintype "bidirectional"))
      (node (ref "U$3") (pin "29") (pinfunction "TP_CS_29") (pintype "bidirectional"))
    )
    (net (code "72") (name "TP_IQR") (class "Default")
      (node (ref "STM") (pin "15") (pinfunction "PC0_15") (pintype "bidirectional"))
      (node (ref "U$3") (pin "28") (pinfunction "TP_IRQ_28") (pintype "bidirectional"))
    )
    (net (code "73") (name "TP_SCK") (class "Default")
      (node (ref "STM") (pin "52") (pinfunction "PB13_52") (pintype "bidirectional"))
      (node (ref "U$3") (pin "30") (pinfunction "TP_SCK_30") (pintype "bidirectional"))
    )
    (net (code "74") (name "TP_SI") (class "Default")
      (node (ref "STM") (pin "53") (pinfunction "PB14_53") (pintype "bidirectional"))
      (node (ref "U$3") (pin "31") (pinfunction "TP_SI_31") (pintype "bidirectional"))
    )
    (net (code "75") (name "TP_SO") (class "Default")
      (node (ref "STM") (pin "54") (pinfunction "PB15_54") (pintype "bidirectional"))
      (node (ref "U$3") (pin "32") (pinfunction "TP_SO_32") (pintype "bidirectional"))
    )
    (net (code "76") (name "USART1_RX") (class "Default")
      (node (ref "STM") (pin "93") (pinfunction "PB7_93") (pintype "bidirectional"))
      (node (ref "U1") (pin "1") (pinfunction "TX_1") (pintype "bidirectional"))
    )
    (net (code "77") (name "USART1_TX") (class "Default")
      (node (ref "STM") (pin "92") (pinfunction "PB6_92") (pintype "bidirectional"))
      (node (ref "U1") (pin "2") (pinfunction "RX_2") (pintype "bidirectional"))
    )
    (net (code "78") (name "unconnected-(R24-Pad2)") (class "Default")
      (node (ref "R24") (pin "2") (pinfunction "2_2") (pintype "passive"))
    )
    (net (code "79") (name "unconnected-(SDCARD2-SHIELD-PadCD2)") (class "Default")
      (node (ref "SDCARD2") (pin "CD2") (pinfunction "SHIELD_CD2") (pintype "bidirectional"))
    )
    (net (code "80") (name "unconnected-(STMD-PA11-Pad70)") (class "Default")
      (node (ref "STM") (pin "70") (pinfunction "PA11_70") (pintype "bidirectional"))
    )
    (net (code "81") (name "unconnected-(STMD-PA12-Pad71)") (class "Default")
      (node (ref "STM") (pin "71") (pinfunction "PA12_71") (pintype "bidirectional"))
    )
    (net (code "82") (name "unconnected-(STMG-PB1-Pad36)") (class "Default")
      (node (ref "STM") (pin "36") (pinfunction "PB1_36") (pintype "bidirectional"))
    )
    (net (code "83") (name "unconnected-(STMG-PB3-Pad89)") (class "Default")
      (node (ref "STM") (pin "89") (pinfunction "PB3_89") (pintype "bidirectional"))
    )
    (net (code "84") (name "unconnected-(STMG-PB4-Pad90)") (class "Default")
      (node (ref "STM") (pin "90") (pinfunction "PB4_90") (pintype "bidirectional"))
    )
    (net (code "85") (name "unconnected-(STMG-PB5-Pad91)") (class "Default")
      (node (ref "STM") (pin "91") (pinfunction "PB5_91") (pintype "bidirectional"))
    )
    (net (code "86") (name "unconnected-(STMH-PC13-Pad7)") (class "Default")
      (node (ref "STM") (pin "7") (pinfunction "PC13_7") (pintype "bidirectional"))
    )
    (net (code "87") (name "unconnected-(STMH-PC14-Pad8)") (class "Default")
      (node (ref "STM") (pin "8") (pinfunction "PC14_8") (pintype "bidirectional"))
    )
    (net (code "88") (name "unconnected-(STMH-PC15-Pad9)") (class "Default")
      (node (ref "STM") (pin "9") (pinfunction "PC15_9") (pintype "bidirectional"))
    )
    (net (code "89") (name "unconnected-(STMI-PC1-Pad16)") (class "Default")
      (node (ref "STM") (pin "16") (pinfunction "PC1_16") (pintype "bidirectional"))
    )
    (net (code "90") (name "unconnected-(STMI-PC2-Pad17)") (class "Default")
      (node (ref "STM") (pin "17") (pinfunction "PC2_17") (pintype "bidirectional"))
    )
    (net (code "91") (name "unconnected-(STMI-PC3-Pad18)") (class "Default")
      (node (ref "STM") (pin "18") (pinfunction "PC3_18") (pintype "bidirectional"))
    )
    (net (code "92") (name "unconnected-(STMJ-PD13-Pad60)") (class "Default")
      (node (ref "STM") (pin "60") (pinfunction "PD13_60") (pintype "bidirectional"))
    )
    (net (code "93") (name "unconnected-(STMK-PD6-Pad87)") (class "Default")
      (node (ref "STM") (pin "87") (pinfunction "PD6_87") (pintype "bidirectional"))
    )
    (net (code "94") (name "unconnected-(STMM-PE0-Pad97)") (class "Default")
      (node (ref "STM") (pin "97") (pinfunction "PE0_97") (pintype "bidirectional"))
    )
    (net (code "95") (name "unconnected-(STMM-PE1-Pad98)") (class "Default")
      (node (ref "STM") (pin "98") (pinfunction "PE1_98") (pintype "bidirectional"))
    )
    (net (code "96") (name "unconnected-(STMM-PE2-Pad1)") (class "Default")
      (node (ref "STM") (pin "1") (pinfunction "PE2_1") (pintype "bidirectional"))
    )
    (net (code "97") (name "unconnected-(STMM-PE3-Pad2)") (class "Default")
      (node (ref "STM") (pin "2") (pinfunction "PE3_2") (pintype "bidirectional"))
    )
    (net (code "98") (name "unconnected-(STMM-PE4-Pad3)") (class "Default")
      (node (ref "STM") (pin "3") (pinfunction "PE4_3") (pintype "bidirectional"))
    )
    (net (code "99") (name "unconnected-(STMM-PE5-Pad4)") (class "Default")
      (node (ref "STM") (pin "4") (pinfunction "PE5_4") (pintype "bidirectional"))
    )
    (net (code "100") (name "unconnected-(STMM-PE6-Pad5)") (class "Default")
      (node (ref "STM") (pin "5") (pinfunction "PE6_5") (pintype "bidirectional"))
    )
    (net (code "101") (name "unconnected-(U$3-3V3-Pad33)") (class "Default")
      (node (ref "U$3") (pin "33") (pinfunction "3V3_33") (pintype "bidirectional"))
    )
    (net (code "102") (name "unconnected-(U$3-NC-Pad24)") (class "Default")
      (node (ref "U$3") (pin "24") (pinfunction "NC_24") (pintype "bidirectional"))
    )
    (net (code "103") (name "unconnected-(U1-AIO0-Pad9)") (class "Default")
      (node (ref "U1") (pin "9") (pinfunction "AIO0_9") (pintype "bidirectional"))
    )
    (net (code "104") (name "unconnected-(U1-AIO1-Pad10)") (class "Default")
      (node (ref "U1") (pin "10") (pinfunction "AIO1_10") (pintype "bidirectional"))
    )
    (net (code "105") (name "unconnected-(U1-CLK-Pad19)") (class "Default")
      (node (ref "U1") (pin "19") (pinfunction "CLK_19") (pintype "bidirectional"))
    )
    (net (code "106") (name "unconnected-(U1-CSB-Pad16)") (class "Default")
      (node (ref "U1") (pin "16") (pinfunction "CSB_16") (pintype "bidirectional"))
    )
    (net (code "107") (name "unconnected-(U1-CTS-Pad3)") (class "Default")
      (node (ref "U1") (pin "3") (pinfunction "CTS_3") (pintype "bidirectional"))
    )
    (net (code "108") (name "unconnected-(U1-GND1-Pad21)") (class "Default")
      (node (ref "U1") (pin "21") (pinfunction "GND1_21") (pintype "bidirectional"))
    )
    (net (code "109") (name "unconnected-(U1-MISO-Pad18)") (class "Default")
      (node (ref "U1") (pin "18") (pinfunction "MISO_18") (pintype "bidirectional"))
    )
    (net (code "110") (name "unconnected-(U1-MOSI-Pad17)") (class "Default")
      (node (ref "U1") (pin "17") (pinfunction "MOSI_17") (pintype "bidirectional"))
    )
    (net (code "111") (name "unconnected-(U1-NC-Pad14)") (class "Default")
      (node (ref "U1") (pin "14") (pinfunction "NC_14") (pintype "bidirectional"))
    )
    (net (code "112") (name "unconnected-(U1-PCM_CLK-Pad5)") (class "Default")
      (node (ref "U1") (pin "5") (pinfunction "PCM_CLK_5") (pintype "bidirectional"))
    )
    (net (code "113") (name "unconnected-(U1-PCM_IN-Pad7)") (class "Default")
      (node (ref "U1") (pin "7") (pinfunction "PCM_IN_7") (pintype "bidirectional"))
    )
    (net (code "114") (name "unconnected-(U1-PCM_OUT-Pad6)") (class "Default")
      (node (ref "U1") (pin "6") (pinfunction "PCM_OUT_6") (pintype "bidirectional"))
    )
    (net (code "115") (name "unconnected-(U1-PCN_SYNC-Pad8)") (class "Default")
      (node (ref "U1") (pin "8") (pinfunction "PCN_SYNC_8") (pintype "bidirectional"))
    )
    (net (code "116") (name "unconnected-(U1-PIO0-Pad23)") (class "Default")
      (node (ref "U1") (pin "23") (pinfunction "PIO0_23") (pintype "bidirectional"))
    )
    (net (code "117") (name "unconnected-(U1-PIO1-Pad24)") (class "Default")
      (node (ref "U1") (pin "24") (pinfunction "PIO1_24") (pintype "bidirectional"))
    )
    (net (code "118") (name "unconnected-(U1-PIO2-Pad25)") (class "Default")
      (node (ref "U1") (pin "25") (pinfunction "PIO2_25") (pintype "bidirectional"))
    )
    (net (code "119") (name "unconnected-(U1-PIO3-Pad26)") (class "Default")
      (node (ref "U1") (pin "26") (pinfunction "PIO3_26") (pintype "bidirectional"))
    )
    (net (code "120") (name "unconnected-(U1-PIO4-Pad27)") (class "Default")
      (node (ref "U1") (pin "27") (pinfunction "PIO4_27") (pintype "bidirectional"))
    )
    (net (code "121") (name "unconnected-(U1-PIO5-Pad28)") (class "Default")
      (node (ref "U1") (pin "28") (pinfunction "PIO5_28") (pintype "bidirectional"))
    )
    (net (code "122") (name "unconnected-(U1-PIO6-Pad29)") (class "Default")
      (node (ref "U1") (pin "29") (pinfunction "PIO6_29") (pintype "bidirectional"))
    )
    (net (code "123") (name "unconnected-(U1-PIO7-Pad30)") (class "Default")
      (node (ref "U1") (pin "30") (pinfunction "PIO7_30") (pintype "bidirectional"))
    )
    (net (code "124") (name "unconnected-(U1-PIO9-Pad32)") (class "Default")
      (node (ref "U1") (pin "32") (pinfunction "PIO9_32") (pintype "bidirectional"))
    )
    (net (code "125") (name "unconnected-(U1-PIO10-Pad33)") (class "Default")
      (node (ref "U1") (pin "33") (pinfunction "PIO10_33") (pintype "bidirectional"))
    )
    (net (code "126") (name "unconnected-(U1-RST-Pad11)") (class "Default")
      (node (ref "U1") (pin "11") (pinfunction "RST_11") (pintype "bidirectional"))
    )
    (net (code "127") (name "unconnected-(U1-RTS-Pad4)") (class "Default")
      (node (ref "U1") (pin "4") (pinfunction "RTS_4") (pintype "bidirectional"))
    )
    (net (code "128") (name "unconnected-(U1-VBUSD+-Pad20)") (class "Default")
      (node (ref "U1") (pin "20") (pinfunction "VBUSD+_20") (pintype "bidirectional"))
    )
    (net (code "129") (name "unconnected-(U1-VBUSD--Pad15)") (class "Default")
      (node (ref "U1") (pin "15") (pinfunction "VBUSD-_15") (pintype "bidirectional"))
    )
  )
)
